# AnalogADCs.net
KiCad netlist of a schematic drawn in Altium Designer
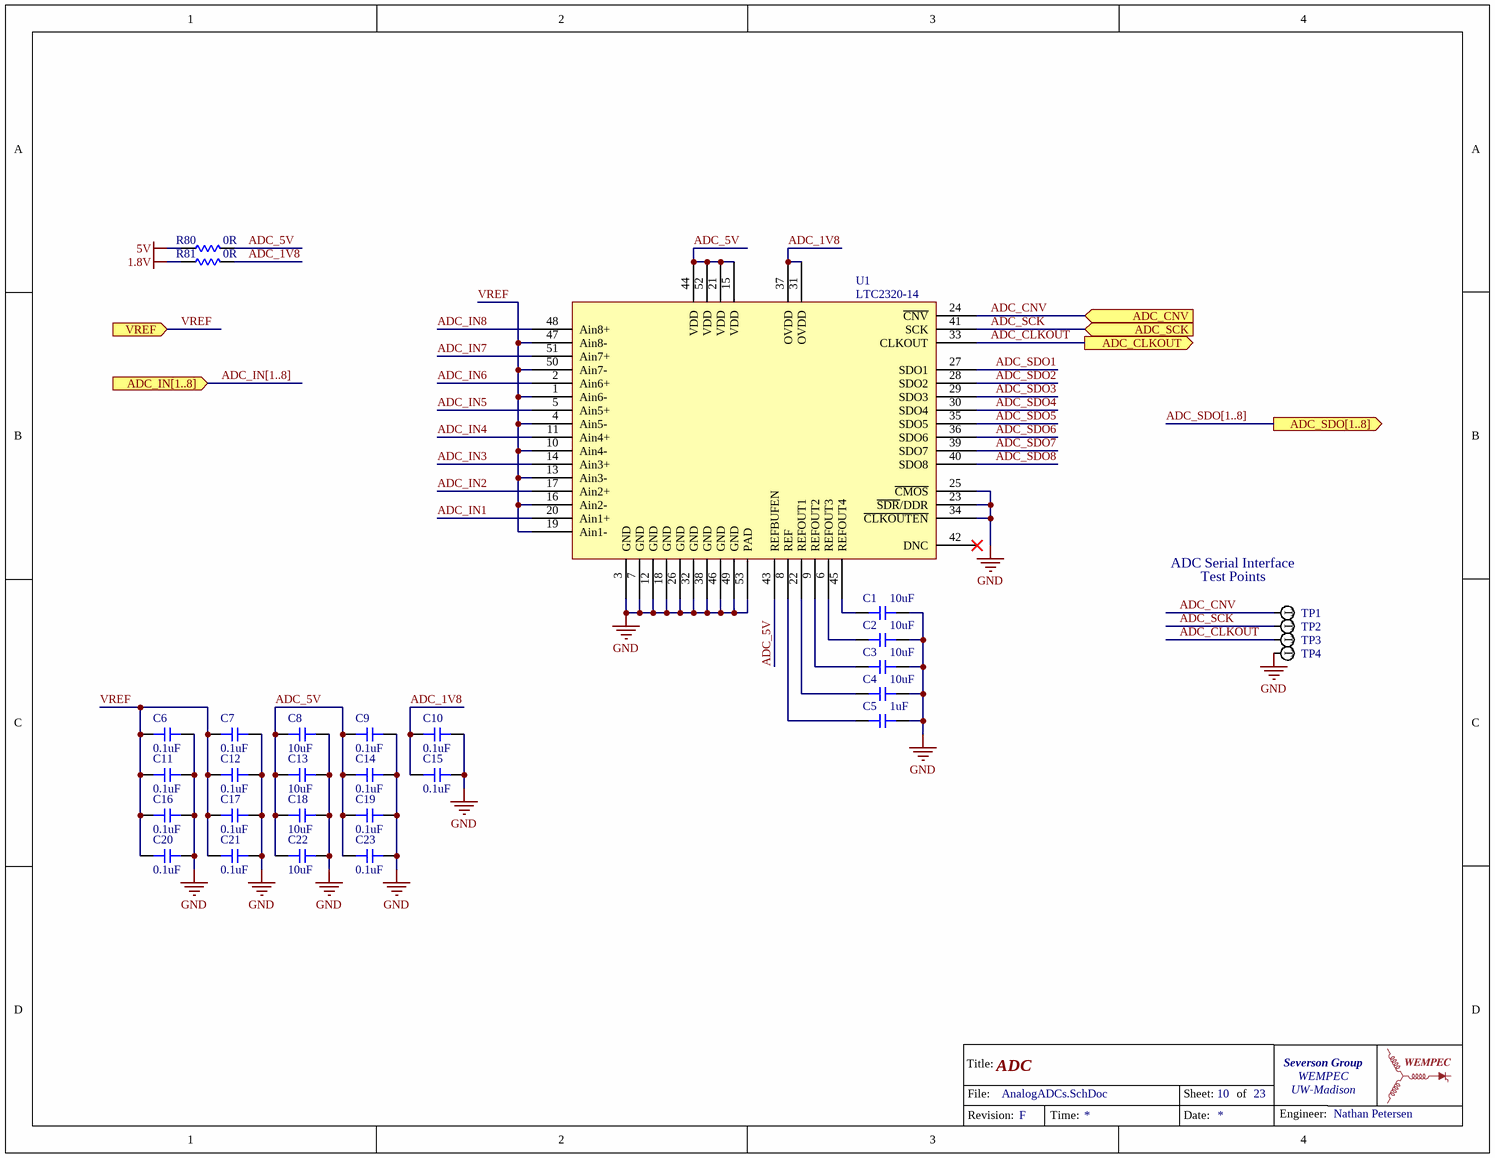
[diagram p0: AnalogADCs.SchDoc]

(export (version "E")
  (design (tool "Eeschema 10.0.6"))
  (components
    (comp (ref "C1")
      (value "10uF")
      (footprint "0603-CAP")
      (description "Capacitor")
      (libsource (lib "AMDC") (part "Capacitor"))
    )
    (comp (ref "C2")
      (value "10uF")
      (footprint "0603-CAP")
      (description "Capacitor")
      (libsource (lib "AMDC") (part "Capacitor"))
    )
    (comp (ref "C3")
      (value "10uF")
      (footprint "0603-CAP")
      (description "Capacitor")
      (libsource (lib "AMDC") (part "Capacitor"))
    )
    (comp (ref "C4")
      (value "10uF")
      (footprint "0603-CAP")
      (description "Capacitor")
      (libsource (lib "AMDC") (part "Capacitor"))
    )
    (comp (ref "C5")
      (value "1uF")
      (footprint "0603-CAP")
      (description "Capacitor")
      (libsource (lib "AMDC") (part "Capacitor"))
    )
    (comp (ref "C6")
      (value "0.1uF")
      (footprint "0603-CAP")
      (description "Capacitor")
      (libsource (lib "AMDC") (part "Capacitor"))
    )
    (comp (ref "C7")
      (value "0.1uF")
      (footprint "0603-CAP")
      (description "Capacitor")
      (libsource (lib "AMDC") (part "Capacitor"))
    )
    (comp (ref "C8")
      (value "10uF")
      (footprint "0603-CAP")
      (description "Capacitor")
      (libsource (lib "AMDC") (part "Capacitor"))
    )
    (comp (ref "C9")
      (value "0.1uF")
      (footprint "0603-CAP")
      (description "Capacitor")
      (libsource (lib "AMDC") (part "Capacitor"))
    )
    (comp (ref "C10")
      (value "0.1uF")
      (footprint "0603-CAP")
      (description "Capacitor")
      (libsource (lib "AMDC") (part "Capacitor"))
    )
    (comp (ref "C11")
      (value "0.1uF")
      (footprint "0603-CAP")
      (description "Capacitor")
      (libsource (lib "AMDC") (part "Capacitor"))
    )
    (comp (ref "C12")
      (value "0.1uF")
      (footprint "0603-CAP")
      (description "Capacitor")
      (libsource (lib "AMDC") (part "Capacitor"))
    )
    (comp (ref "C13")
      (value "10uF")
      (footprint "0603-CAP")
      (description "Capacitor")
      (libsource (lib "AMDC") (part "Capacitor"))
    )
    (comp (ref "C14")
      (value "0.1uF")
      (footprint "0603-CAP")
      (description "Capacitor")
      (libsource (lib "AMDC") (part "Capacitor"))
    )
    (comp (ref "C15")
      (value "0.1uF")
      (footprint "0603-CAP")
      (description "Capacitor")
      (libsource (lib "AMDC") (part "Capacitor"))
    )
    (comp (ref "C16")
      (value "0.1uF")
      (footprint "0603-CAP")
      (description "Capacitor")
      (libsource (lib "AMDC") (part "Capacitor"))
    )
    (comp (ref "C17")
      (value "0.1uF")
      (footprint "0603-CAP")
      (description "Capacitor")
      (libsource (lib "AMDC") (part "Capacitor"))
    )
    (comp (ref "C18")
      (value "10uF")
      (footprint "0603-CAP")
      (description "Capacitor")
      (libsource (lib "AMDC") (part "Capacitor"))
    )
    (comp (ref "C19")
      (value "0.1uF")
      (footprint "0603-CAP")
      (description "Capacitor")
      (libsource (lib "AMDC") (part "Capacitor"))
    )
    (comp (ref "C20")
      (value "0.1uF")
      (footprint "0603-CAP")
      (description "Capacitor")
      (libsource (lib "AMDC") (part "Capacitor"))
    )
    (comp (ref "C21")
      (value "0.1uF")
      (footprint "0603-CAP")
      (description "Capacitor")
      (libsource (lib "AMDC") (part "Capacitor"))
    )
    (comp (ref "C22")
      (value "10uF")
      (footprint "0603-CAP")
      (description "Capacitor")
      (libsource (lib "AMDC") (part "Capacitor"))
    )
    (comp (ref "C23")
      (value "0.1uF")
      (footprint "0603-CAP")
      (description "Capacitor")
      (libsource (lib "AMDC") (part "Capacitor"))
    )
    (comp (ref "R80")
      (value "0R")
      (footprint "1206-RES")
      (description "Resistor")
      (libsource (lib "AMDC") (part "Resistor"))
    )
    (comp (ref "R81")
      (value "0R")
      (footprint "1206-RES")
      (description "Resistor")
      (libsource (lib "AMDC") (part "Resistor"))
    )
    (comp (ref "TP1") (value "Test Point") (footprint "RCU-0C") (libsource (lib "AMDC") (part "Test Point")))
    (comp (ref "TP2") (value "Test Point") (footprint "RCU-0C") (libsource (lib "AMDC") (part "Test Point")))
    (comp (ref "TP3") (value "Test Point") (footprint "RCU-0C") (libsource (lib "AMDC") (part "Test Point")))
    (comp (ref "TP4") (value "Test Point") (footprint "RCU-0C") (libsource (lib "AMDC") (part "Test Point")))
    (comp (ref "U1")
      (value "LTC2320-14")
      (footprint "QFN50P700X800X80_HS-53N")
      (description "IC ADC 14BIT 1.5MSPS SAR 52QFN - 14 Bit Analog to Digital Converter 8 Input 4 SAR 52-QFN (7x8)")
      (libsource (lib "AMDC") (part "LTC2320-14"))
    )
  )
  (nets
    (net (code "1") (name "/ADC_1V8") (class "Default")
      (node (ref "C10") (pin "1") (pinfunction "1_1") (pintype "passive"))
      (node (ref "C15") (pin "1") (pinfunction "1_1") (pintype "passive"))
      (node (ref "R81") (pin "2") (pinfunction "2_2") (pintype "passive"))
      (node (ref "U1") (pin "31") (pinfunction "OVDD_31") (pintype "passive"))
      (node (ref "U1") (pin "37") (pinfunction "OVDD_37") (pintype "passive"))
    )
    (net (code "2") (name "/ADC_5V") (class "Default")
      (node (ref "C13") (pin "1") (pinfunction "1_1") (pintype "passive"))
      (node (ref "C14") (pin "1") (pinfunction "1_1") (pintype "passive"))
      (node (ref "C18") (pin "1") (pinfunction "1_1") (pintype "passive"))
      (node (ref "C19") (pin "1") (pinfunction "1_1") (pintype "passive"))
      (node (ref "C22") (pin "1") (pinfunction "1_1") (pintype "passive"))
      (node (ref "C23") (pin "1") (pinfunction "1_1") (pintype "passive"))
      (node (ref "C8") (pin "1") (pinfunction "1_1") (pintype "passive"))
      (node (ref "C9") (pin "1") (pinfunction "1_1") (pintype "passive"))
      (node (ref "R80") (pin "2") (pinfunction "2_2") (pintype "passive"))
      (node (ref "U1") (pin "15") (pinfunction "VDD_15") (pintype "passive"))
      (node (ref "U1") (pin "21") (pinfunction "VDD_21") (pintype "passive"))
      (node (ref "U1") (pin "43") (pinfunction "REFBUFEN_43") (pintype "passive"))
      (node (ref "U1") (pin "44") (pinfunction "VDD_44") (pintype "passive"))
      (node (ref "U1") (pin "52") (pinfunction "VDD_52") (pintype "passive"))
    )
    (net (code "3") (name "/ADC_CLKOUT") (class "Default")
      (node (ref "TP3") (pin "1") (pinfunction "1_1") (pintype "passive"))
      (node (ref "U1") (pin "33") (pinfunction "CLKOUT_33") (pintype "passive"))
    )
    (net (code "4") (name "/ADC_CNV") (class "Default")
      (node (ref "TP1") (pin "1") (pinfunction "1_1") (pintype "passive"))
      (node (ref "U1") (pin "24") (pinfunction "~{CNV}_24") (pintype "passive"))
    )
    (net (code "5") (name "/ADC_IN1") (class "Default")
      (node (ref "U1") (pin "20") (pinfunction "Ain1+_20") (pintype "passive"))
    )
    (net (code "6") (name "/ADC_IN2") (class "Default")
      (node (ref "U1") (pin "17") (pinfunction "Ain2+_17") (pintype "passive"))
    )
    (net (code "7") (name "/ADC_IN3") (class "Default")
      (node (ref "U1") (pin "14") (pinfunction "Ain3+_14") (pintype "passive"))
    )
    (net (code "8") (name "/ADC_IN4") (class "Default")
      (node (ref "U1") (pin "11") (pinfunction "Ain4+_11") (pintype "passive"))
    )
    (net (code "9") (name "/ADC_IN5") (class "Default")
      (node (ref "U1") (pin "5") (pinfunction "Ain5+_5") (pintype "passive"))
    )
    (net (code "10") (name "/ADC_IN6") (class "Default")
      (node (ref "U1") (pin "2") (pinfunction "Ain6+_2") (pintype "passive"))
    )
    (net (code "11") (name "/ADC_IN7") (class "Default")
      (node (ref "U1") (pin "51") (pinfunction "Ain7+_51") (pintype "passive"))
    )
    (net (code "12") (name "/ADC_IN8") (class "Default")
      (node (ref "U1") (pin "48") (pinfunction "Ain8+_48") (pintype "passive"))
    )
    (net (code "14") (name "/ADC_SCK") (class "Default")
      (node (ref "TP2") (pin "1") (pinfunction "1_1") (pintype "passive"))
      (node (ref "U1") (pin "41") (pinfunction "SCK_41") (pintype "passive"))
    )
    (net (code "15") (name "/ADC_SDO1") (class "Default")
      (node (ref "U1") (pin "27") (pinfunction "SDO1_27") (pintype "passive"))
    )
    (net (code "16") (name "/ADC_SDO2") (class "Default")
      (node (ref "U1") (pin "28") (pinfunction "SDO2_28") (pintype "passive"))
    )
    (net (code "17") (name "/ADC_SDO3") (class "Default")
      (node (ref "U1") (pin "29") (pinfunction "SDO3_29") (pintype "passive"))
    )
    (net (code "18") (name "/ADC_SDO4") (class "Default")
      (node (ref "U1") (pin "30") (pinfunction "SDO4_30") (pintype "passive"))
    )
    (net (code "19") (name "/ADC_SDO5") (class "Default")
      (node (ref "U1") (pin "35") (pinfunction "SDO5_35") (pintype "passive"))
    )
    (net (code "20") (name "/ADC_SDO6") (class "Default")
      (node (ref "U1") (pin "36") (pinfunction "SDO6_36") (pintype "passive"))
    )
    (net (code "21") (name "/ADC_SDO7") (class "Default")
      (node (ref "U1") (pin "39") (pinfunction "SDO7_39") (pintype "passive"))
    )
    (net (code "22") (name "/ADC_SDO8") (class "Default")
      (node (ref "U1") (pin "40") (pinfunction "SDO8_40") (pintype "passive"))
    )
    (net (code "24") (name "/VREF") (class "Default")
      (node (ref "C11") (pin "1") (pinfunction "1_1") (pintype "passive"))
      (node (ref "C12") (pin "1") (pinfunction "1_1") (pintype "passive"))
      (node (ref "C16") (pin "1") (pinfunction "1_1") (pintype "passive"))
      (node (ref "C17") (pin "1") (pinfunction "1_1") (pintype "passive"))
      (node (ref "C20") (pin "1") (pinfunction "1_1") (pintype "passive"))
      (node (ref "C21") (pin "1") (pinfunction "1_1") (pintype "passive"))
      (node (ref "C6") (pin "1") (pinfunction "1_1") (pintype "passive"))
      (node (ref "C7") (pin "1") (pinfunction "1_1") (pintype "passive"))
      (node (ref "U1") (pin "1") (pinfunction "Ain6-_1") (pintype "passive"))
      (node (ref "U1") (pin "10") (pinfunction "Ain4-_10") (pintype "passive"))
      (node (ref "U1") (pin "13") (pinfunction "Ain3-_13") (pintype "passive"))
      (node (ref "U1") (pin "16") (pinfunction "Ain2-_16") (pintype "passive"))
      (node (ref "U1") (pin "19") (pinfunction "Ain1-_19") (pintype "passive"))
      (node (ref "U1") (pin "4") (pinfunction "Ain5-_4") (pintype "passive"))
      (node (ref "U1") (pin "47") (pinfunction "Ain8-_47") (pintype "passive"))
      (node (ref "U1") (pin "50") (pinfunction "Ain7-_50") (pintype "passive"))
    )
    (net (code "25") (name "1.8V") (class "Default")
      (node (ref "R81") (pin "1") (pinfunction "1_1") (pintype "passive"))
    )
    (net (code "26") (name "5V") (class "Default")
      (node (ref "R80") (pin "1") (pinfunction "1_1") (pintype "passive"))
    )
    (net (code "27") (name "GND") (class "Default")
      (node (ref "C1") (pin "2") (pinfunction "2_2") (pintype "passive"))
      (node (ref "C10") (pin "2") (pinfunction "2_2") (pintype "passive"))
      (node (ref "C11") (pin "2") (pinfunction "2_2") (pintype "passive"))
      (node (ref "C12") (pin "2") (pinfunction "2_2") (pintype "passive"))
      (node (ref "C13") (pin "2") (pinfunction "2_2") (pintype "passive"))
      (node (ref "C14") (pin "2") (pinfunction "2_2") (pintype "passive"))
      (node (ref "C15") (pin "2") (pinfunction "2_2") (pintype "passive"))
      (node (ref "C16") (pin "2") (pinfunction "2_2") (pintype "passive"))
      (node (ref "C17") (pin "2") (pinfunction "2_2") (pintype "passive"))
      (node (ref "C18") (pin "2") (pinfunction "2_2") (pintype "passive"))
      (node (ref "C19") (pin "2") (pinfunction "2_2") (pintype "passive"))
      (node (ref "C2") (pin "2") (pinfunction "2_2") (pintype "passive"))
      (node (ref "C20") (pin "2") (pinfunction "2_2") (pintype "passive"))
      (node (ref "C21") (pin "2") (pinfunction "2_2") (pintype "passive"))
      (node (ref "C22") (pin "2") (pinfunction "2_2") (pintype "passive"))
      (node (ref "C23") (pin "2") (pinfunction "2_2") (pintype "passive"))
      (node (ref "C3") (pin "2") (pinfunction "2_2") (pintype "passive"))
      (node (ref "C4") (pin "2") (pinfunction "2_2") (pintype "passive"))
      (node (ref "C5") (pin "2") (pinfunction "2_2") (pintype "passive"))
      (node (ref "C6") (pin "2") (pinfunction "2_2") (pintype "passive"))
      (node (ref "C7") (pin "2") (pinfunction "2_2") (pintype "passive"))
      (node (ref "C8") (pin "2") (pinfunction "2_2") (pintype "passive"))
      (node (ref "C9") (pin "2") (pinfunction "2_2") (pintype "passive"))
      (node (ref "TP4") (pin "1") (pinfunction "1_1") (pintype "passive"))
      (node (ref "U1") (pin "12") (pinfunction "GND_12") (pintype "passive"))
      (node (ref "U1") (pin "18") (pinfunction "GND_18") (pintype "passive"))
      (node (ref "U1") (pin "23") (pinfunction "~{SDR}/DDR_23") (pintype "passive"))
      (node (ref "U1") (pin "25") (pinfunction "~{CMOS}_25") (pintype "passive"))
      (node (ref "U1") (pin "26") (pinfunction "GND_26") (pintype "passive"))
      (node (ref "U1") (pin "3") (pinfunction "GND_3") (pintype "passive"))
      (node (ref "U1") (pin "32") (pinfunction "GND_32") (pintype "passive"))
      (node (ref "U1") (pin "34") (pinfunction "~{CLKOUTEN}_34") (pintype "passive"))
      (node (ref "U1") (pin "38") (pinfunction "GND_38") (pintype "passive"))
      (node (ref "U1") (pin "46") (pinfunction "GND_46") (pintype "passive"))
      (node (ref "U1") (pin "49") (pinfunction "GND_49") (pintype "passive"))
      (node (ref "U1") (pin "53") (pinfunction "PAD_53") (pintype "passive"))
      (node (ref "U1") (pin "7") (pinfunction "GND_7") (pintype "passive"))
    )
    (net (code "28") (name "Net-(U1-REF)") (class "Default")
      (node (ref "C5") (pin "1") (pinfunction "1_1") (pintype "passive"))
      (node (ref "U1") (pin "8") (pinfunction "REF_8") (pintype "passive"))
    )
    (net (code "29") (name "Net-(U1-REFOUT1)") (class "Default")
      (node (ref "C4") (pin "1") (pinfunction "1_1") (pintype "passive"))
      (node (ref "U1") (pin "22") (pinfunction "REFOUT1_22") (pintype "passive"))
    )
    (net (code "30") (name "Net-(U1-REFOUT2)") (class "Default")
      (node (ref "C3") (pin "1") (pinfunction "1_1") (pintype "passive"))
      (node (ref "U1") (pin "9") (pinfunction "REFOUT2_9") (pintype "passive"))
    )
    (net (code "31") (name "Net-(U1-REFOUT3)") (class "Default")
      (node (ref "C2") (pin "1") (pinfunction "1_1") (pintype "passive"))
      (node (ref "U1") (pin "6") (pinfunction "REFOUT3_6") (pintype "passive"))
    )
    (net (code "32") (name "Net-(U1-REFOUT4)") (class "Default")
      (node (ref "C1") (pin "1") (pinfunction "1_1") (pintype "passive"))
      (node (ref "U1") (pin "45") (pinfunction "REFOUT4_45") (pintype "passive"))
    )
    (net (code "33") (name "unconnected-(U1-DNC-Pad42)") (class "Default")
      (node (ref "U1") (pin "42") (pinfunction "DNC_42") (pintype "passive+no_connect"))
    )
  )
)
